# as3320-BandPass-Dev2.net
KiCad netlist of a schematic drawn in EAGLE
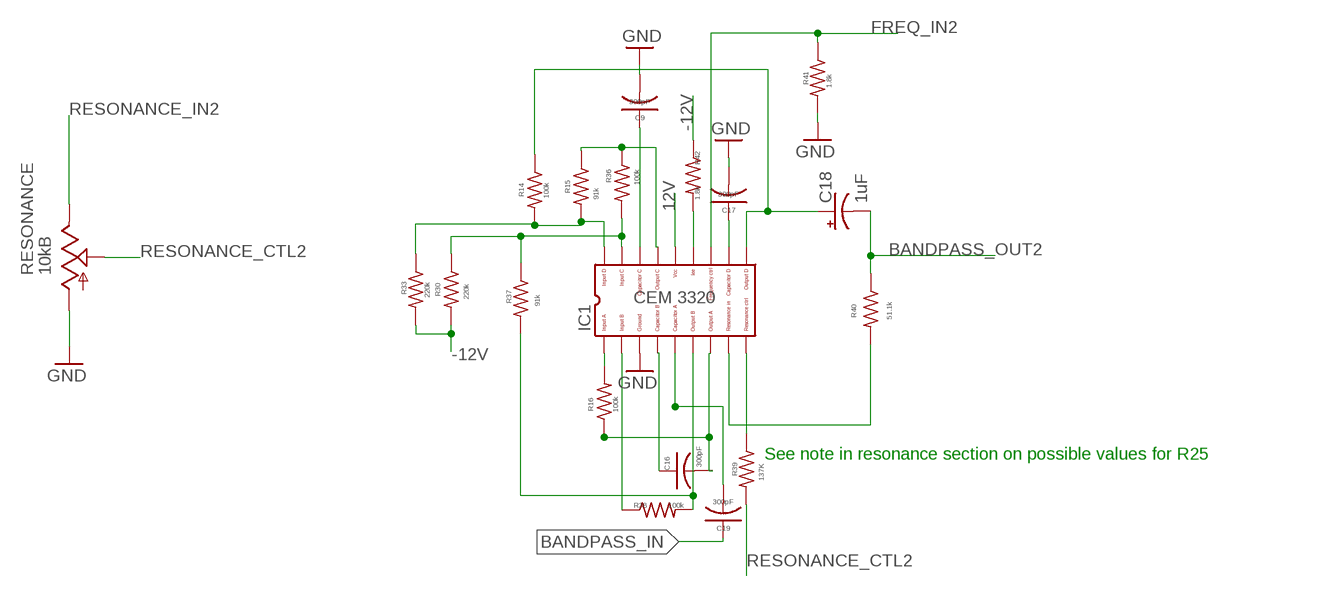
[diagram p0: schematic, sheet 1]
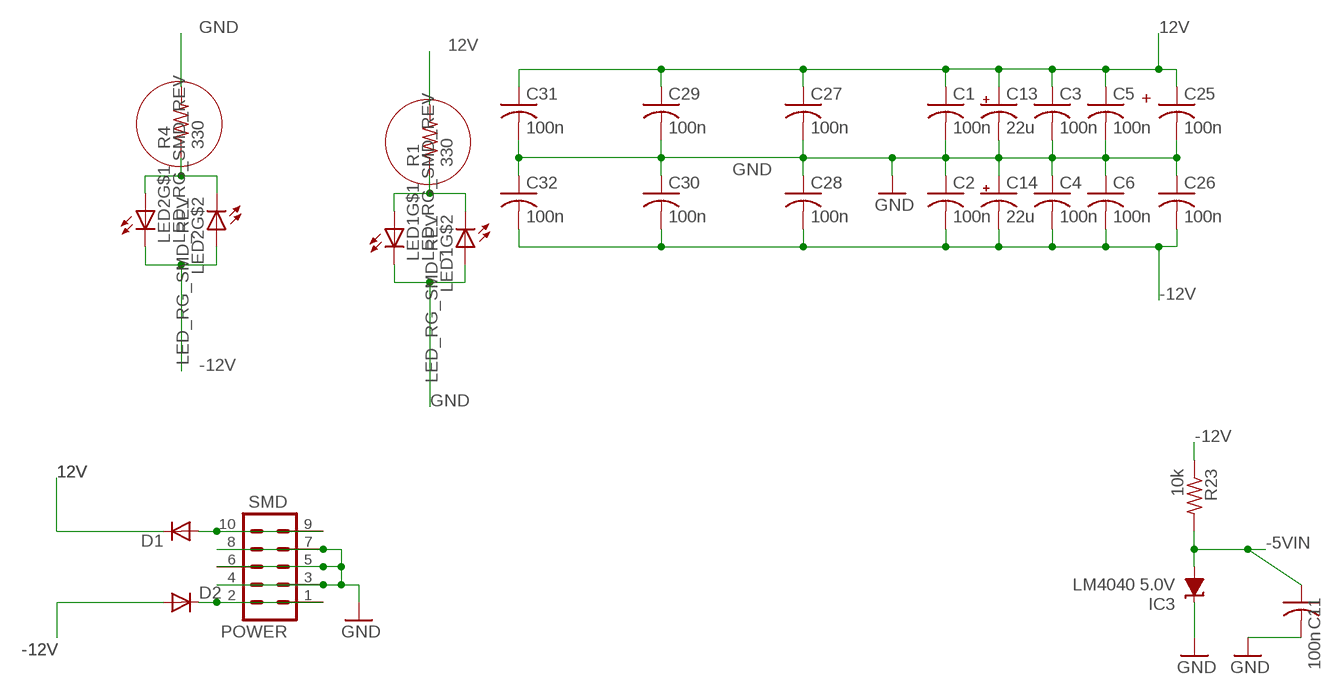
[diagram p1: schematic, sheet 2]
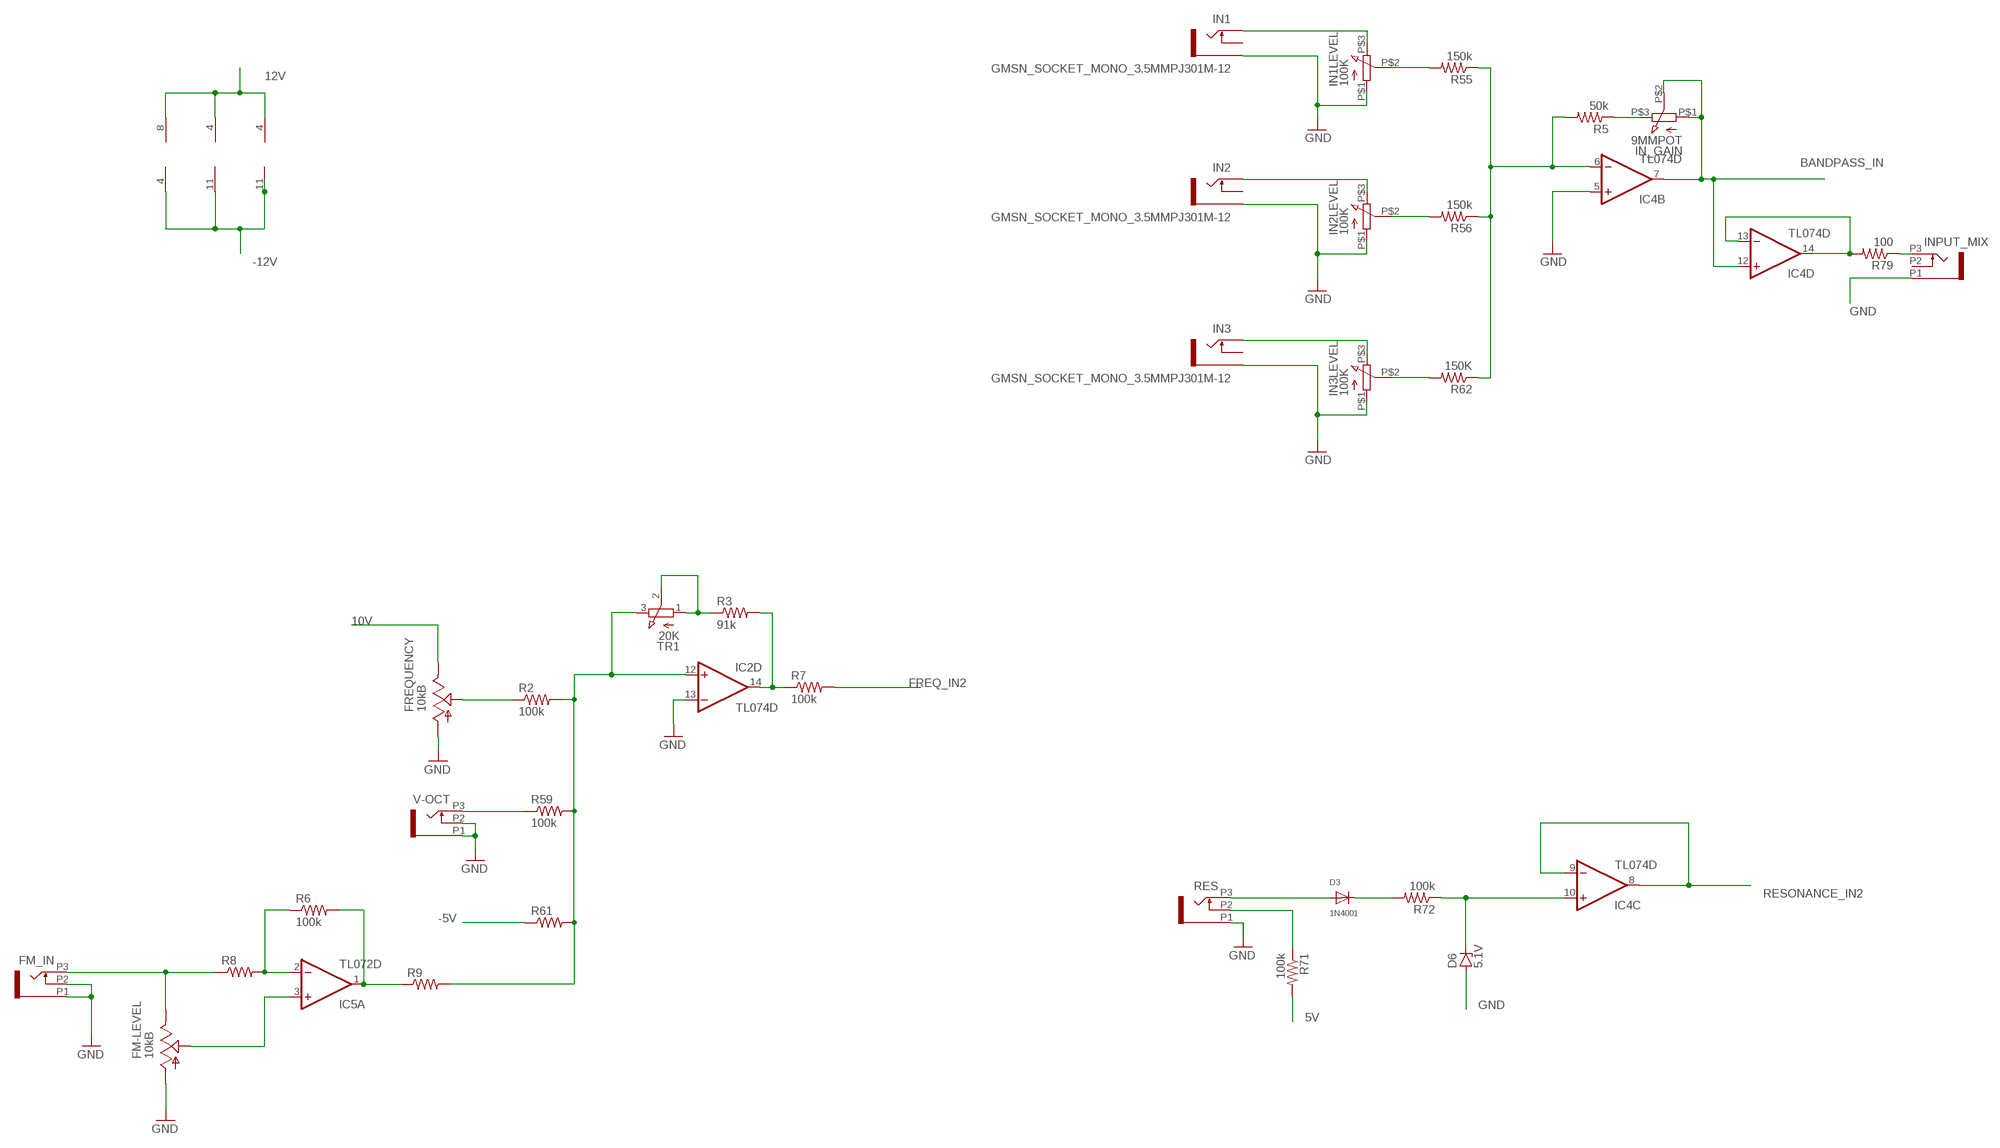
[diagram p2: schematic, sheet 3]
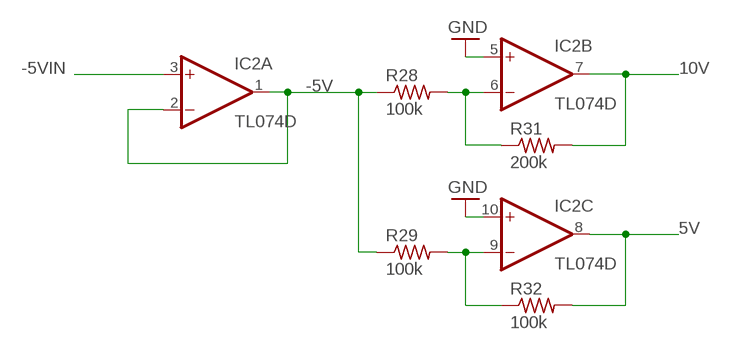
[diagram p3: schematic, sheet 4]
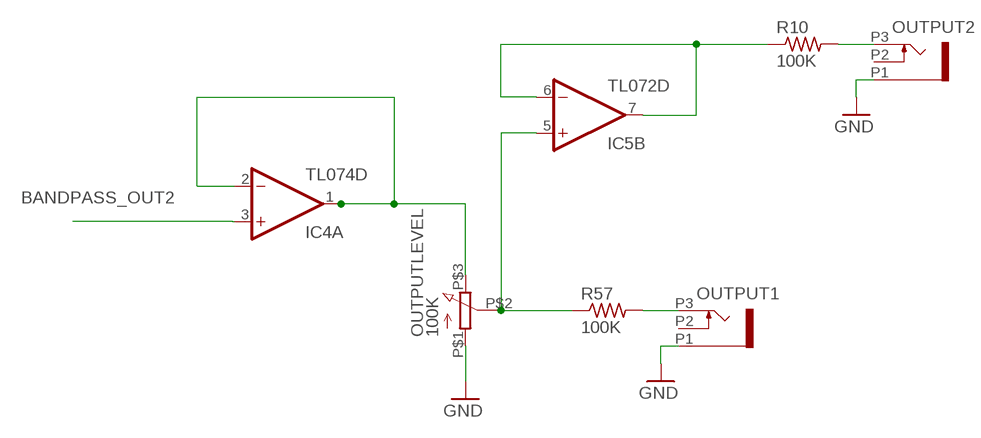
[diagram p4: schematic, sheet 5]

(export (version "E")
  (design (tool "Eeschema 10.0.6"))
  (components
    (comp (ref "C1")
      (value "100n")
      (footprint "eagle-import:C0805K")
      (libsource (lib "eagle-import") (part "C-USC0805K"))
    )
    (comp (ref "C2")
      (value "100n")
      (footprint "eagle-import:C0805K")
      (libsource (lib "eagle-import") (part "C-USC0805K"))
    )
    (comp (ref "C3")
      (value "100n")
      (footprint "eagle-import:C0805K")
      (libsource (lib "eagle-import") (part "C-USC0805K"))
    )
    (comp (ref "C4")
      (value "100n")
      (footprint "eagle-import:C0805K")
      (libsource (lib "eagle-import") (part "C-USC0805K"))
    )
    (comp (ref "C5")
      (value "100n")
      (footprint "eagle-import:C0805K")
      (libsource (lib "eagle-import") (part "C-USC0805K"))
    )
    (comp (ref "C6")
      (value "100n")
      (footprint "eagle-import:C0805K")
      (libsource (lib "eagle-import") (part "C-USC0805K"))
    )
    (comp (ref "C11")
      (value "100n")
      (footprint "eagle-import:GMSN_C0805K")
      (libsource (lib "eagle-import") (part "GMSN_C-USC0805K"))
    )
    (comp (ref "C13")
      (value "22u")
      (footprint "eagle-import:PANASONIC_B")
      (libsource (lib "eagle-import") (part "CPOL-USB"))
    )
    (comp (ref "C14")
      (value "22u")
      (footprint "eagle-import:PANASONIC_B")
      (libsource (lib "eagle-import") (part "CPOL-USB"))
    )
    (comp (ref "C25")
      (value "100n")
      (footprint "eagle-import:C0805K")
      (libsource (lib "eagle-import") (part "C-USC0805K"))
    )
    (comp (ref "C26")
      (value "100n")
      (footprint "eagle-import:C0805K")
      (libsource (lib "eagle-import") (part "C-USC0805K"))
    )
    (comp (ref "C27")
      (value "100n")
      (footprint "eagle-import:C0805K")
      (libsource (lib "eagle-import") (part "C-USC0805K"))
    )
    (comp (ref "C28")
      (value "100n")
      (footprint "eagle-import:C0805K")
      (libsource (lib "eagle-import") (part "C-USC0805K"))
    )
    (comp (ref "C29")
      (value "100n")
      (footprint "eagle-import:C0805K")
      (libsource (lib "eagle-import") (part "C-USC0805K"))
    )
    (comp (ref "C30")
      (value "100n")
      (footprint "eagle-import:C0805K")
      (libsource (lib "eagle-import") (part "C-USC0805K"))
    )
    (comp (ref "C31")
      (value "100n")
      (footprint "eagle-import:C0805K")
      (libsource (lib "eagle-import") (part "C-USC0805K"))
    )
    (comp (ref "C32")
      (value "100n")
      (footprint "eagle-import:C0805K")
      (libsource (lib "eagle-import") (part "C-USC0805K"))
    )
    (comp (ref "D1")
      (value "1N5819HW")
      (footprint "eagle-import:SOD123")
      (libsource (lib "eagle-import") (part "DIODE-SOD123"))
    )
    (comp (ref "D2")
      (value "1N5819HW")
      (footprint "eagle-import:SOD123")
      (libsource (lib "eagle-import") (part "DIODE-SOD123"))
    )
    (comp (ref "IC3")
      (value "LM4040 5.0V")
      (footprint "eagle-import:DBZ_R-PDSO-G3")
      (libsource (lib "eagle-import") (part "LM4041DBZC12"))
    )
    (comp (ref "LED1")
      (value "LED_RG_SMD_REV")
      (footprint "eagle-import:LSG_T77K")
      (fields (field (name "RS-PART") "915-4828"))
      (libsource (lib "eagle-import") (part "LED_RG_SMD_REV"))
    )
    (comp (ref "LED2")
      (value "LED_RG_SMD_REV")
      (footprint "eagle-import:LSG_T77K")
      (libsource (lib "eagle-import") (part "LED_RG_SMD_REV"))
    )
    (comp (ref "POWER")
      (value "SMD")
      (footprint "eagle-import:2X5-SHROUDED_SMD")
      (fields (field (name "RS-PART") "828-1783"))
      (libsource (lib "eagle-import") (part "CONN_05X2SHD_SMD"))
    )
    (comp (ref "R1")
      (value "330")
      (footprint "eagle-import:GMSN_M0805")
      (libsource (lib "eagle-import") (part "GMSN_R-US_M0805"))
    )
    (comp (ref "R4")
      (value "330")
      (footprint "eagle-import:GMSN_M0805")
      (fields (field (name "RS-PART") "915-4828"))
      (libsource (lib "eagle-import") (part "GMSN_R-US_M0805"))
    )
    (comp (ref "R23")
      (value "10k")
      (footprint "eagle-import:GMSN_M0805")
      (libsource (lib "eagle-import") (part "GMSN_R-US_M0805"))
    )
    (comp (ref "C9")
      (value "300pF")
      (footprint "eagle-import:C0805K")
      (libsource (lib "eagle-import") (part "C-USC0805K"))
    )
    (comp (ref "C16")
      (value "300pF")
      (footprint "eagle-import:C0805K")
      (libsource (lib "eagle-import") (part "C-USC0805K"))
    )
    (comp (ref "C17")
      (value "300pF")
      (footprint "eagle-import:C0805K")
      (libsource (lib "eagle-import") (part "C-USC0805K"))
    )
    (comp (ref "C18")
      (value "1uF")
      (footprint "eagle-import:PANASONIC_B")
      (libsource (lib "eagle-import") (part "rcl_334_CPOL-USB"))
    )
    (comp (ref "C19")
      (value "300pF")
      (footprint "eagle-import:C0805K")
      (libsource (lib "eagle-import") (part "C-USC0805K"))
    )
    (comp (ref "IC1")
      (value "CEM3320")
      (footprint "eagle-import:DIL18")
      (libsource (lib "eagle-import") (part "CEM3320"))
    )
    (comp (ref "R14")
      (value "100k")
      (footprint "eagle-import:GMSN_M0805")
      (libsource (lib "eagle-import") (part "GMSN_R-US_M0805"))
    )
    (comp (ref "R15")
      (value "91k")
      (footprint "eagle-import:GMSN_M0805")
      (libsource (lib "eagle-import") (part "GMSN_R-US_M0805"))
    )
    (comp (ref "R16")
      (value "100k")
      (footprint "eagle-import:GMSN_M0805")
      (libsource (lib "eagle-import") (part "GMSN_R-US_M0805"))
    )
    (comp (ref "R30")
      (value "220k")
      (footprint "eagle-import:GMSN_M0805")
      (libsource (lib "eagle-import") (part "GMSN_R-US_M0805"))
    )
    (comp (ref "R33")
      (value "220k")
      (footprint "eagle-import:GMSN_M0805")
      (libsource (lib "eagle-import") (part "GMSN_R-US_M0805"))
    )
    (comp (ref "R36")
      (value "100k")
      (footprint "eagle-import:GMSN_M0805")
      (libsource (lib "eagle-import") (part "GMSN_R-US_M0805"))
    )
    (comp (ref "R37")
      (value "91k")
      (footprint "eagle-import:GMSN_M0805")
      (libsource (lib "eagle-import") (part "GMSN_R-US_M0805"))
    )
    (comp (ref "R38")
      (value "100k")
      (footprint "eagle-import:GMSN_M0805")
      (libsource (lib "eagle-import") (part "GMSN_R-US_M0805"))
    )
    (comp (ref "R39")
      (value "137K")
      (footprint "eagle-import:GMSN_M0805")
      (libsource (lib "eagle-import") (part "GMSN_R-US_M0805"))
    )
    (comp (ref "R40")
      (value "51.1k")
      (footprint "eagle-import:GMSN_M0805")
      (libsource (lib "eagle-import") (part "GMSN_R-US_M0805"))
    )
    (comp (ref "R41")
      (value "1.8k")
      (footprint "eagle-import:GMSN_M0805")
      (libsource (lib "eagle-import") (part "GMSN_R-US_M0805"))
    )
    (comp (ref "R42")
      (value "1.8k")
      (footprint "eagle-import:GMSN_M0805")
      (libsource (lib "eagle-import") (part "GMSN_R-US_M0805"))
    )
    (comp (ref "RESONANCE")
      (value "10kB")
      (footprint "eagle-import:ALPS_POT_VERTICAL")
      (libsource (lib "eagle-import") (part "POT_USVERTICAL"))
    )
    (comp (ref "D3")
      (value "1N4001")
      (footprint "eagle-import:SMADIODE")
      (libsource (lib "eagle-import") (part "DIODESMA"))
    )
    (comp (ref "D6")
      (value "5.1V")
      (footprint "eagle-import:SOT23")
      (fields (field (name "RS-PART") "816-7962"))
      (libsource (lib "eagle-import") (part "ZENER-DIODESOT23"))
    )
    (comp (ref "FM-LEVEL")
      (value "10kB")
      (footprint "eagle-import:ALPS_POT_VERTICAL")
      (libsource (lib "eagle-import") (part "POT_USVERTICAL"))
    )
    (comp (ref "FM_IN")
      (value "PJ301_THONKICONN6")
      (footprint "eagle-import:WQP_PJ_301M6")
      (libsource (lib "eagle-import") (part "PJ301_THONKICONN6"))
    )
    (comp (ref "FREQUENCY")
      (value "10kB")
      (footprint "eagle-import:ALPS_POT_VERTICAL")
      (libsource (lib "eagle-import") (part "POT_USVERTICAL"))
    )
    (comp (ref "IC2")
      (value "TL074D")
      (footprint "eagle-import:SO14")
      (libsource (lib "eagle-import") (part "linear_262_TL074D"))
    )
    (comp (ref "IC4")
      (value "TL074D")
      (footprint "eagle-import:SO14")
      (libsource (lib "eagle-import") (part "TL074D"))
    )
    (comp (ref "IC5")
      (value "TL072D")
      (footprint "eagle-import:SO08")
      (libsource (lib "eagle-import") (part "TL072D"))
    )
    (comp (ref "IN1")
      (value "GMSN_SOCKET_MONO_3.5MMPJ301M-12")
      (footprint "eagle-import:GMSN_PJ301M-12")
      (libsource (lib "eagle-import") (part "GMSN_SOCKET_MONO_3.5MMPJ301M-12"))
    )
    (comp (ref "IN1LEVEL")
      (value "100K")
      (footprint "eagle-import:POT")
      (libsource (lib "eagle-import") (part "9MMPOT"))
    )
    (comp (ref "IN2")
      (value "GMSN_SOCKET_MONO_3.5MMPJ301M-12")
      (footprint "eagle-import:GMSN_PJ301M-12")
      (libsource (lib "eagle-import") (part "GMSN_SOCKET_MONO_3.5MMPJ301M-12"))
    )
    (comp (ref "IN2LEVEL")
      (value "100K")
      (footprint "eagle-import:POT")
      (libsource (lib "eagle-import") (part "9MMPOT"))
    )
    (comp (ref "IN3")
      (value "GMSN_SOCKET_MONO_3.5MMPJ301M-12")
      (footprint "eagle-import:GMSN_PJ301M-12")
      (libsource (lib "eagle-import") (part "GMSN_SOCKET_MONO_3.5MMPJ301M-12"))
    )
    (comp (ref "IN3LEVEL")
      (value "100K")
      (footprint "eagle-import:POT")
      (libsource (lib "eagle-import") (part "9MMPOT"))
    )
    (comp (ref "INPUT_MIX")
      (value "PJ301_THONKICONN6")
      (footprint "eagle-import:WQP_PJ_301M6")
      (libsource (lib "eagle-import") (part "PJ301_THONKICONN6"))
    )
    (comp (ref "IN_GAIN")
      (value "9MMPOT")
      (footprint "eagle-import:POT")
      (libsource (lib "eagle-import") (part "9MMPOT"))
    )
    (comp (ref "R2")
      (value "100k")
      (footprint "eagle-import:GMSN_M0805")
      (libsource (lib "eagle-import") (part "GMSN_R-US_M0805"))
    )
    (comp (ref "R3")
      (value "91k")
      (footprint "eagle-import:GMSN_M0805")
      (libsource (lib "eagle-import") (part "GMSN_R-US_M0805"))
    )
    (comp (ref "R5")
      (value "50k")
      (footprint "eagle-import:GMSN_M0805")
      (libsource (lib "eagle-import") (part "GMSN_R-US_M0805"))
    )
    (comp (ref "R6")
      (value "100k")
      (footprint "eagle-import:GMSN_M0805")
      (libsource (lib "eagle-import") (part "GMSN_R-US_M0805"))
    )
    (comp (ref "R7")
      (value "100k")
      (footprint "eagle-import:GMSN_M0805")
      (libsource (lib "eagle-import") (part "GMSN_R-US_M0805"))
    )
    (comp (ref "R8")
      (value "62k")
      (footprint "eagle-import:GMSN_M0805")
      (libsource (lib "eagle-import") (part "GMSN_R-US_M0805"))
    )
    (comp (ref "R9")
      (value "62k")
      (footprint "eagle-import:GMSN_M0805")
      (libsource (lib "eagle-import") (part "GMSN_R-US_M0805"))
    )
    (comp (ref "R55")
      (value "150k")
      (footprint "eagle-import:R0805")
      (libsource (lib "eagle-import") (part "GMSN_R-US_R0805"))
    )
    (comp (ref "R56")
      (value "150k")
      (footprint "eagle-import:R0805")
      (libsource (lib "eagle-import") (part "GMSN_R-US_R0805"))
    )
    (comp (ref "R59")
      (value "100k")
      (footprint "eagle-import:GMSN_M0805")
      (libsource (lib "eagle-import") (part "GMSN_R-US_M0805"))
    )
    (comp (ref "R61")
      (value "62k")
      (footprint "eagle-import:GMSN_M0805")
      (libsource (lib "eagle-import") (part "GMSN_R-US_M0805"))
    )
    (comp (ref "R62")
      (value "150K")
      (footprint "eagle-import:R0805")
      (libsource (lib "eagle-import") (part "GMSN_R-US_R0805"))
    )
    (comp (ref "R71")
      (value "100k")
      (footprint "eagle-import:R0805")
      (libsource (lib "eagle-import") (part "GMSN_R-US_R0805"))
    )
    (comp (ref "R72")
      (value "100k")
      (footprint "eagle-import:GMSN_M0805")
      (libsource (lib "eagle-import") (part "GMSN_R-US_M0805"))
    )
    (comp (ref "R79")
      (value "100")
      (footprint "eagle-import:GMSN_M0805")
      (libsource (lib "eagle-import") (part "GMSN_R-US_M0805"))
    )
    (comp (ref "RES")
      (value "PJ301_THONKICONN6")
      (footprint "eagle-import:WQP_PJ_301M6")
      (libsource (lib "eagle-import") (part "PJ301_THONKICONN6"))
    )
    (comp (ref "TR1")
      (value "20K")
      (footprint "eagle-import:TRIMMER_TH3")
      (libsource (lib "eagle-import") (part "TRIMMER_TH3"))
    )
    (comp (ref "V-OCT")
      (value "PJ301_THONKICONN6")
      (footprint "eagle-import:WQP_PJ_301M6")
      (libsource (lib "eagle-import") (part "PJ301_THONKICONN6"))
    )
    (comp (ref "OUTPUT1")
      (value "PJ301_THONKICONN6")
      (footprint "eagle-import:WQP_PJ_301M6")
      (libsource (lib "eagle-import") (part "PJ301_THONKICONN6"))
    )
    (comp (ref "OUTPUT2")
      (value "PJ301_THONKICONN6")
      (footprint "eagle-import:WQP_PJ_301M6")
      (libsource (lib "eagle-import") (part "PJ301_THONKICONN6"))
    )
    (comp (ref "OUTPUTLEVEL")
      (value "100K")
      (footprint "eagle-import:POT")
      (libsource (lib "eagle-import") (part "9MMPOT"))
    )
    (comp (ref "R10")
      (value "100K")
      (footprint "eagle-import:GMSN_M0805")
      (libsource (lib "eagle-import") (part "GMSN_R-US_M0805"))
    )
    (comp (ref "R57")
      (value "100K")
      (footprint "eagle-import:GMSN_M0805")
      (libsource (lib "eagle-import") (part "GMSN_R-US_M0805"))
    )
    (comp (ref "R28")
      (value "100k")
      (footprint "eagle-import:GMSN_M0805")
      (libsource (lib "eagle-import") (part "GMSN_R-US_M0805"))
    )
    (comp (ref "R29")
      (value "100k")
      (footprint "eagle-import:GMSN_M0805")
      (libsource (lib "eagle-import") (part "GMSN_R-US_M0805"))
    )
    (comp (ref "R31")
      (value "200k")
      (footprint "eagle-import:GMSN_M0805")
      (libsource (lib "eagle-import") (part "GMSN_R-US_M0805"))
    )
    (comp (ref "R32")
      (value "100k")
      (footprint "eagle-import:GMSN_M0805")
      (libsource (lib "eagle-import") (part "GMSN_R-US_M0805"))
    )
  )
  (nets
    (net (code "1") (name "-5V") (class "Default")
      (node (ref "IC2") (pin "1") (pinfunction "OUT_1") (pintype "output"))
      (node (ref "IC2") (pin "2") (pinfunction "-IN_2") (pintype "input"))
      (node (ref "R28") (pin "1") (pinfunction "1_1") (pintype "passive"))
      (node (ref "R29") (pin "1") (pinfunction "1_1") (pintype "passive"))
      (node (ref "R61") (pin "1") (pinfunction "1_1") (pintype "passive"))
    )
    (net (code "2") (name "-5VIN") (class "Default")
      (node (ref "C11") (pin "1") (pinfunction "1_1") (pintype "passive"))
      (node (ref "IC2") (pin "3") (pinfunction "+IN_3") (pintype "input"))
      (node (ref "IC3") (pin "2") (pinfunction "A_2") (pintype "passive"))
      (node (ref "R23") (pin "2") (pinfunction "2_2") (pintype "passive"))
    )
    (net (code "3") (name "-12V") (class "Default")
      (node (ref "C14") (pin "-") (pinfunction "-_-") (pintype "passive"))
      (node (ref "C2") (pin "2") (pinfunction "2_2") (pintype "passive"))
      (node (ref "C26") (pin "2") (pinfunction "2_2") (pintype "passive"))
      (node (ref "C28") (pin "2") (pinfunction "2_2") (pintype "passive"))
      (node (ref "C30") (pin "2") (pinfunction "2_2") (pintype "passive"))
      (node (ref "C32") (pin "2") (pinfunction "2_2") (pintype "passive"))
      (node (ref "C4") (pin "2") (pinfunction "2_2") (pintype "passive"))
      (node (ref "C6") (pin "2") (pinfunction "2_2") (pintype "passive"))
      (node (ref "D2") (pin "A") (pinfunction "A_A") (pintype "passive"))
      (node (ref "IC2") (pin "11") (pinfunction "V-_11") (pintype "power_in"))
      (node (ref "IC4") (pin "11") (pinfunction "V-_11") (pintype "power_in"))
      (node (ref "IC5") (pin "4") (pinfunction "V-_4") (pintype "power_in"))
      (node (ref "LED2") (pin "1") (pinfunction "C_1") (pintype "passive"))
      (node (ref "LED2") (pin "4") (pinfunction "A_4") (pintype "passive"))
      (node (ref "R23") (pin "1") (pinfunction "1_1") (pintype "passive"))
      (node (ref "R30") (pin "2") (pinfunction "2_2") (pintype "passive"))
      (node (ref "R33") (pin "2") (pinfunction "2_2") (pintype "passive"))
      (node (ref "R42") (pin "1") (pinfunction "1_1") (pintype "passive"))
    )
    (net (code "4") (name "5V") (class "Default")
      (node (ref "IC2") (pin "8") (pinfunction "OUT_8") (pintype "output"))
      (node (ref "R32") (pin "2") (pinfunction "2_2") (pintype "passive"))
      (node (ref "R71") (pin "2") (pinfunction "2_2") (pintype "passive"))
    )
    (net (code "5") (name "10V") (class "Default")
      (node (ref "FREQUENCY") (pin "P$1") (pinfunction "E_P$1") (pintype "passive"))
      (node (ref "IC2") (pin "7") (pinfunction "OUT_7") (pintype "output"))
      (node (ref "R31") (pin "2") (pinfunction "2_2") (pintype "passive"))
    )
    (net (code "6") (name "12V") (class "Default")
      (node (ref "C1") (pin "1") (pinfunction "1_1") (pintype "passive"))
      (node (ref "C13") (pin "+") (pinfunction "+_+") (pintype "passive"))
      (node (ref "C25") (pin "1") (pinfunction "1_1") (pintype "passive"))
      (node (ref "C27") (pin "1") (pinfunction "1_1") (pintype "passive"))
      (node (ref "C29") (pin "1") (pinfunction "1_1") (pintype "passive"))
      (node (ref "C3") (pin "1") (pinfunction "1_1") (pintype "passive"))
      (node (ref "C31") (pin "1") (pinfunction "1_1") (pintype "passive"))
      (node (ref "C5") (pin "1") (pinfunction "1_1") (pintype "passive"))
      (node (ref "D1") (pin "C") (pinfunction "C_C") (pintype "passive"))
      (node (ref "IC1") (pin "14") (pinfunction "14_14") (pintype "power_in"))
      (node (ref "IC2") (pin "4") (pinfunction "V+_4") (pintype "power_in"))
      (node (ref "IC4") (pin "4") (pinfunction "V+_4") (pintype "power_in"))
      (node (ref "IC5") (pin "8") (pinfunction "V+_8") (pintype "power_in"))
      (node (ref "R1") (pin "2") (pinfunction "2_2") (pintype "passive"))
    )
    (net (code "7") (name "BANDPASS_IN") (class "Default")
      (node (ref "C19") (pin "1") (pinfunction "1_1") (pintype "passive"))
      (node (ref "IC4") (pin "12") (pinfunction "+IN_12") (pintype "input"))
      (node (ref "IC4") (pin "7") (pinfunction "OUT_7") (pintype "output"))
      (node (ref "IN_GAIN") (pin "P$1") (pinfunction "1_P$1") (pintype "passive"))
      (node (ref "IN_GAIN") (pin "P$2") (pinfunction "2_P$2") (pintype "passive"))
    )
    (net (code "8") (name "BANDPASS_OUT2") (class "Default")
      (node (ref "C18") (pin "-") (pinfunction "-_-") (pintype "passive"))
      (node (ref "IC4") (pin "3") (pinfunction "+IN_3") (pintype "input"))
      (node (ref "R40") (pin "1") (pinfunction "1_1") (pintype "passive"))
    )
    (net (code "9") (name "FREQ_IN2") (class "Default")
      (node (ref "IC1") (pin "12") (pinfunction "12_12") (pintype "bidirectional"))
      (node (ref "R41") (pin "1") (pinfunction "1_1") (pintype "passive"))
      (node (ref "R7") (pin "2") (pinfunction "2_2") (pintype "passive"))
    )
    (net (code "10") (name "GND") (class "Default")
      (node (ref "C1") (pin "2") (pinfunction "2_2") (pintype "passive"))
      (node (ref "C11") (pin "2") (pinfunction "2_2") (pintype "passive"))
      (node (ref "C13") (pin "-") (pinfunction "-_-") (pintype "passive"))
      (node (ref "C14") (pin "+") (pinfunction "+_+") (pintype "passive"))
      (node (ref "C17") (pin "2") (pinfunction "2_2") (pintype "passive"))
      (node (ref "C2") (pin "1") (pinfunction "1_1") (pintype "passive"))
      (node (ref "C25") (pin "2") (pinfunction "2_2") (pintype "passive"))
      (node (ref "C26") (pin "1") (pinfunction "1_1") (pintype "passive"))
      (node (ref "C27") (pin "2") (pinfunction "2_2") (pintype "passive"))
      (node (ref "C28") (pin "1") (pinfunction "1_1") (pintype "passive"))
      (node (ref "C29") (pin "2") (pinfunction "2_2") (pintype "passive"))
      (node (ref "C3") (pin "2") (pinfunction "2_2") (pintype "passive"))
      (node (ref "C30") (pin "1") (pinfunction "1_1") (pintype "passive"))
      (node (ref "C31") (pin "2") (pinfunction "2_2") (pintype "passive"))
      (node (ref "C32") (pin "1") (pinfunction "1_1") (pintype "passive"))
      (node (ref "C4") (pin "1") (pinfunction "1_1") (pintype "passive"))
      (node (ref "C5") (pin "2") (pinfunction "2_2") (pintype "passive"))
      (node (ref "C6") (pin "1") (pinfunction "1_1") (pintype "passive"))
      (node (ref "C9") (pin "2") (pinfunction "2_2") (pintype "passive"))
      (node (ref "D6") (pin "1") (pinfunction "A_1") (pintype "passive"))
      (node (ref "FM-LEVEL") (pin "P$3") (pinfunction "A_P$3") (pintype "passive"))
      (node (ref "FM_IN") (pin "P1") (pinfunction "1_P1") (pintype "passive"))
      (node (ref "FM_IN") (pin "P2") (pinfunction "2_P2") (pintype "passive"))
      (node (ref "FREQUENCY") (pin "P$3") (pinfunction "A_P$3") (pintype "passive"))
      (node (ref "IC1") (pin "3") (pinfunction "3_3") (pintype "power_in"))
      (node (ref "IC2") (pin "10") (pinfunction "+IN_10") (pintype "input"))
      (node (ref "IC2") (pin "13") (pinfunction "-IN_13") (pintype "input"))
      (node (ref "IC2") (pin "5") (pinfunction "+IN_5") (pintype "input"))
      (node (ref "IC3") (pin "1") (pinfunction "C_1") (pintype "passive"))
      (node (ref "IC4") (pin "5") (pinfunction "+IN_5") (pintype "input"))
      (node (ref "IN1") (pin "GND") (pinfunction "SLEEVE_GND") (pintype "passive"))
      (node (ref "IN1LEVEL") (pin "P$1") (pinfunction "1_P$1") (pintype "passive"))
      (node (ref "IN2") (pin "GND") (pinfunction "SLEEVE_GND") (pintype "passive"))
      (node (ref "IN2LEVEL") (pin "P$1") (pinfunction "1_P$1") (pintype "passive"))
      (node (ref "IN3") (pin "GND") (pinfunction "SLEEVE_GND") (pintype "passive"))
      (node (ref "IN3LEVEL") (pin "P$1") (pinfunction "1_P$1") (pintype "passive"))
      (node (ref "INPUT_MIX") (pin "P1") (pinfunction "1_P1") (pintype "passive"))
      (node (ref "LED1") (pin "1") (pinfunction "C_1") (pintype "passive"))
      (node (ref "LED1") (pin "4") (pinfunction "A_4") (pintype "passive"))
      (node (ref "OUTPUT1") (pin "P1") (pinfunction "1_P1") (pintype "passive"))
      (node (ref "OUTPUT2") (pin "P1") (pinfunction "1_P1") (pintype "passive"))
      (node (ref "OUTPUTLEVEL") (pin "P$1") (pinfunction "1_P$1") (pintype "passive"))
      (node (ref "POWER") (pin "3") (pinfunction "3_3") (pintype "passive"))
      (node (ref "POWER") (pin "4") (pinfunction "4_4") (pintype "passive"))
      (node (ref "POWER") (pin "5") (pinfunction "5_5") (pintype "passive"))
      (node (ref "POWER") (pin "6") (pinfunction "6_6") (pintype "passive"))
      (node (ref "POWER") (pin "7") (pinfunction "7_7") (pintype "passive"))
      (node (ref "POWER") (pin "8") (pinfunction "8_8") (pintype "passive"))
      (node (ref "R4") (pin "2") (pinfunction "2_2") (pintype "passive"))
      (node (ref "R41") (pin "2") (pinfunction "2_2") (pintype "passive"))
      (node (ref "RES") (pin "P1") (pinfunction "1_P1") (pintype "passive"))
      (node (ref "RESONANCE") (pin "P$3") (pinfunction "A_P$3") (pintype "passive"))
      (node (ref "V-OCT") (pin "P1") (pinfunction "1_P1") (pintype "passive"))
      (node (ref "V-OCT") (pin "P2") (pinfunction "2_P2") (pintype "passive"))
    )
    (net (code "11") (name "Net-(C9-Pad1)") (class "Default")
      (node (ref "C9") (pin "1") (pinfunction "1_1") (pintype "passive"))
      (node (ref "IC1") (pin "16") (pinfunction "16_16") (pintype "bidirectional"))
    )
    (net (code "12") (name "Net-(C16-Pad1)") (class "Default")
      (node (ref "C16") (pin "1") (pinfunction "1_1") (pintype "passive"))
      (node (ref "IC1") (pin "4") (pinfunction "4_4") (pintype "bidirectional"))
    )
    (net (code "13") (name "Net-(C16-Pad2)") (class "Default")
      (node (ref "C16") (pin "2") (pinfunction "2_2") (pintype "passive"))
      (node (ref "IC1") (pin "7") (pinfunction "7_7") (pintype "output"))
      (node (ref "R16") (pin "1") (pinfunction "1_1") (pintype "passive"))
    )
    (net (code "14") (name "Net-(C17-Pad1)") (class "Default")
      (node (ref "C17") (pin "1") (pinfunction "1_1") (pintype "passive"))
      (node (ref "IC1") (pin "11") (pinfunction "11_11") (pintype "output"))
    )
    (net (code "15") (name "Net-(C18-Pad+)") (class "Default")
      (node (ref "C18") (pin "+") (pinfunction "+_+") (pintype "passive"))
      (node (ref "IC1") (pin "10") (pinfunction "10_10") (pintype "output"))
      (node (ref "R14") (pin "1") (pinfunction "1_1") (pintype "passive"))
    )
    (net (code "16") (name "Net-(C19-Pad2)") (class "Default")
      (node (ref "C19") (pin "2") (pinfunction "2_2") (pintype "passive"))
      (node (ref "IC1") (pin "5") (pinfunction "5_5") (pintype "bidirectional"))
    )
    (net (code "17") (name "Net-(D1-PadA)") (class "Default")
      (node (ref "D1") (pin "A") (pinfunction "A_A") (pintype "passive"))
      (node (ref "POWER") (pin "10") (pinfunction "10_10") (pintype "passive"))
      (node (ref "POWER") (pin "9") (pinfunction "9_9") (pintype "passive"))
    )
    (net (code "18") (name "Net-(D2-PadC)") (class "Default")
      (node (ref "D2") (pin "C") (pinfunction "C_C") (pintype "passive"))
      (node (ref "POWER") (pin "1") (pinfunction "1_1") (pintype "passive"))
      (node (ref "POWER") (pin "2") (pinfunction "2_2") (pintype "passive"))
    )
    (net (code "19") (name "Net-(D3-PadC)") (class "Default")
      (node (ref "D3") (pin "C") (pinfunction "C_C") (pintype "passive"))
      (node (ref "R72") (pin "2") (pinfunction "2_2") (pintype "passive"))
    )
    (net (code "20") (name "Net-(D6-C)") (class "Default")
      (node (ref "D6") (pin "3") (pinfunction "C_3") (pintype "passive"))
      (node (ref "IC4") (pin "10") (pinfunction "+IN_10") (pintype "input"))
      (node (ref "R72") (pin "1") (pinfunction "1_1") (pintype "passive"))
    )
    (net (code "21") (name "Net-(FM-LEVEL-E)") (class "Default")
      (node (ref "FM-LEVEL") (pin "P$1") (pinfunction "E_P$1") (pintype "passive"))
      (node (ref "FM_IN") (pin "P3") (pinfunction "3_P3") (pintype "passive"))
      (node (ref "R8") (pin "1") (pinfunction "1_1") (pintype "passive"))
    )
    (net (code "22") (name "Net-(FM-LEVEL-S)") (class "Default")
      (node (ref "FM-LEVEL") (pin "P$2") (pinfunction "S_P$2") (pintype "passive"))
      (node (ref "IC5") (pin "3") (pinfunction "+IN_3") (pintype "input"))
    )
    (net (code "23") (name "Net-(FREQUENCY-S)") (class "Default")
      (node (ref "FREQUENCY") (pin "P$2") (pinfunction "S_P$2") (pintype "passive"))
      (node (ref "R2") (pin "1") (pinfunction "1_1") (pintype "passive"))
    )
    (net (code "24") (name "Net-(IC1-Pad1)") (class "Default")
      (node (ref "IC1") (pin "1") (pinfunction "1_1") (pintype "input"))
      (node (ref "R16") (pin "2") (pinfunction "2_2") (pintype "passive"))
    )
    (net (code "25") (name "Net-(IC1-Pad2)") (class "Default")
      (node (ref "IC1") (pin "2") (pinfunction "2_2") (pintype "input"))
      (node (ref "R38") (pin "1") (pinfunction "1_1") (pintype "passive"))
    )
    (net (code "26") (name "Net-(IC1-Pad6)") (class "Default")
      (node (ref "IC1") (pin "6") (pinfunction "6_6") (pintype "output"))
      (node (ref "R37") (pin "2") (pinfunction "2_2") (pintype "passive"))
      (node (ref "R38") (pin "2") (pinfunction "2_2") (pintype "passive"))
    )
    (net (code "27") (name "Net-(IC1-Pad8)") (class "Default")
      (node (ref "IC1") (pin "8") (pinfunction "8_8") (pintype "input"))
      (node (ref "R40") (pin "2") (pinfunction "2_2") (pintype "passive"))
    )
    (net (code "28") (name "Net-(IC1-Pad9)") (class "Default")
      (node (ref "IC1") (pin "9") (pinfunction "9_9") (pintype "input"))
      (node (ref "R39") (pin "1") (pinfunction "1_1") (pintype "passive"))
    )
    (net (code "29") (name "Net-(IC1-Pad13)") (class "Default")
      (node (ref "IC1") (pin "13") (pinfunction "13_13") (pintype "power_in"))
      (node (ref "R42") (pin "2") (pinfunction "2_2") (pintype "passive"))
    )
    (net (code "30") (name "Net-(IC1-Pad15)") (class "Default")
      (node (ref "IC1") (pin "15") (pinfunction "15_15") (pintype "output"))
      (node (ref "R15") (pin "1") (pinfunction "1_1") (pintype "passive"))
      (node (ref "R36") (pin "1") (pinfunction "1_1") (pintype "passive"))
    )
    (net (code "31") (name "Net-(IC1-Pad17)") (class "Default")
      (node (ref "IC1") (pin "17") (pinfunction "17_17") (pintype "input"))
      (node (ref "R30") (pin "1") (pinfunction "1_1") (pintype "passive"))
      (node (ref "R36") (pin "2") (pinfunction "2_2") (pintype "passive"))
      (node (ref "R37") (pin "1") (pinfunction "1_1") (pintype "passive"))
    )
    (net (code "32") (name "Net-(IC1-Pad18)") (class "Default")
      (node (ref "IC1") (pin "18") (pinfunction "18_18") (pintype "input"))
      (node (ref "R14") (pin "2") (pinfunction "2_2") (pintype "passive"))
      (node (ref "R15") (pin "2") (pinfunction "2_2") (pintype "passive"))
      (node (ref "R33") (pin "1") (pinfunction "1_1") (pintype "passive"))
    )
    (net (code "33") (name "Net-(IC2B--IN)") (class "Default")
      (node (ref "IC2") (pin "6") (pinfunction "-IN_6") (pintype "input"))
      (node (ref "R28") (pin "2") (pinfunction "2_2") (pintype "passive"))
      (node (ref "R31") (pin "1") (pinfunction "1_1") (pintype "passive"))
    )
    (net (code "34") (name "Net-(IC2C--IN)") (class "Default")
      (node (ref "IC2") (pin "9") (pinfunction "-IN_9") (pintype "input"))
      (node (ref "R29") (pin "2") (pinfunction "2_2") (pintype "passive"))
      (node (ref "R32") (pin "1") (pinfunction "1_1") (pintype "passive"))
    )
    (net (code "35") (name "Net-(IC2D-+IN)") (class "Default")
      (node (ref "IC2") (pin "12") (pinfunction "+IN_12") (pintype "input"))
      (node (ref "R2") (pin "2") (pinfunction "2_2") (pintype "passive"))
      (node (ref "R59") (pin "2") (pinfunction "2_2") (pintype "passive"))
      (node (ref "R61") (pin "2") (pinfunction "2_2") (pintype "passive"))
      (node (ref "R9") (pin "2") (pinfunction "2_2") (pintype "passive"))
      (node (ref "TR1") (pin "3") (pinfunction "3_3") (pintype "passive"))
    )
    (net (code "36") (name "Net-(IC2D-OUT)") (class "Default")
      (node (ref "IC2") (pin "14") (pinfunction "OUT_14") (pintype "output"))
      (node (ref "R3") (pin "2") (pinfunction "2_2") (pintype "passive"))
      (node (ref "R7") (pin "1") (pinfunction "1_1") (pintype "passive"))
    )
    (net (code "37") (name "Net-(IC4A--IN)") (class "Default")
      (node (ref "IC4") (pin "1") (pinfunction "OUT_1") (pintype "output"))
      (node (ref "IC4") (pin "2") (pinfunction "-IN_2") (pintype "input"))
      (node (ref "OUTPUTLEVEL") (pin "P$3") (pinfunction "3_P$3") (pintype "passive"))
    )
    (net (code "38") (name "Net-(IC4B--IN)") (class "Default")
      (node (ref "IC4") (pin "6") (pinfunction "-IN_6") (pintype "input"))
      (node (ref "R5") (pin "2") (pinfunction "2_2") (pintype "passive"))
      (node (ref "R55") (pin "1") (pinfunction "1_1") (pintype "passive"))
      (node (ref "R56") (pin "1") (pinfunction "1_1") (pintype "passive"))
      (node (ref "R62") (pin "1") (pinfunction "1_1") (pintype "passive"))
    )
    (net (code "39") (name "Net-(IC4D--IN)") (class "Default")
      (node (ref "IC4") (pin "13") (pinfunction "-IN_13") (pintype "input"))
      (node (ref "IC4") (pin "14") (pinfunction "OUT_14") (pintype "output"))
      (node (ref "R79") (pin "2") (pinfunction "2_2") (pintype "passive"))
    )
    (net (code "40") (name "Net-(IC5A--IN)") (class "Default")
      (node (ref "IC5") (pin "2") (pinfunction "-IN_2") (pintype "input"))
      (node (ref "R6") (pin "1") (pinfunction "1_1") (pintype "passive"))
      (node (ref "R8") (pin "2") (pinfunction "2_2") (pintype "passive"))
    )
    (net (code "41") (name "Net-(IC5A-OUT)") (class "Default")
      (node (ref "IC5") (pin "1") (pinfunction "OUT_1") (pintype "output"))
      (node (ref "R6") (pin "2") (pinfunction "2_2") (pintype "passive"))
      (node (ref "R9") (pin "1") (pinfunction "1_1") (pintype "passive"))
    )
    (net (code "42") (name "Net-(IC5B-+IN)") (class "Default")
      (node (ref "IC5") (pin "5") (pinfunction "+IN_5") (pintype "input"))
      (node (ref "OUTPUTLEVEL") (pin "P$2") (pinfunction "2_P$2") (pintype "passive"))
      (node (ref "R57") (pin "1") (pinfunction "1_1") (pintype "passive"))
    )
    (net (code "43") (name "Net-(IC5B--IN)") (class "Default")
      (node (ref "IC5") (pin "6") (pinfunction "-IN_6") (pintype "input"))
      (node (ref "IC5") (pin "7") (pinfunction "OUT_7") (pintype "output"))
      (node (ref "R10") (pin "1") (pinfunction "1_1") (pintype "passive"))
    )
    (net (code "44") (name "Net-(IN1LEVEL-2)") (class "Default")
      (node (ref "IN1LEVEL") (pin "P$2") (pinfunction "2_P$2") (pintype "passive"))
      (node (ref "R55") (pin "2") (pinfunction "2_2") (pintype "passive"))
    )
    (net (code "45") (name "Net-(IN1LEVEL-3)") (class "Default")
      (node (ref "IN1") (pin "TIP") (pinfunction "TIP_TIP") (pintype "passive"))
      (node (ref "IN1LEVEL") (pin "P$3") (pinfunction "3_P$3") (pintype "passive"))
    )
    (net (code "46") (name "Net-(IN2LEVEL-2)") (class "Default")
      (node (ref "IN2LEVEL") (pin "P$2") (pinfunction "2_P$2") (pintype "passive"))
      (node (ref "R56") (pin "2") (pinfunction "2_2") (pintype "passive"))
    )
    (net (code "47") (name "Net-(IN2LEVEL-3)") (class "Default")
      (node (ref "IN2") (pin "TIP") (pinfunction "TIP_TIP") (pintype "passive"))
      (node (ref "IN2LEVEL") (pin "P$3") (pinfunction "3_P$3") (pintype "passive"))
    )
    (net (code "48") (name "Net-(IN3LEVEL-2)") (class "Default")
      (node (ref "IN3LEVEL") (pin "P$2") (pinfunction "2_P$2") (pintype "passive"))
      (node (ref "R62") (pin "2") (pinfunction "2_2") (pintype "passive"))
    )
    (net (code "49") (name "Net-(IN3LEVEL-3)") (class "Default")
      (node (ref "IN3") (pin "TIP") (pinfunction "TIP_TIP") (pintype "passive"))
      (node (ref "IN3LEVEL") (pin "P$3") (pinfunction "3_P$3") (pintype "passive"))
    )
    (net (code "50") (name "Net-(INPUT_MIX-3)") (class "Default")
      (node (ref "INPUT_MIX") (pin "P3") (pinfunction "3_P3") (pintype "passive"))
      (node (ref "R79") (pin "1") (pinfunction "1_1") (pintype "passive"))
    )
    (net (code "51") (name "Net-(IN_GAIN-3)") (class "Default")
      (node (ref "IN_GAIN") (pin "P$3") (pinfunction "3_P$3") (pintype "passive"))
      (node (ref "R5") (pin "1") (pinfunction "1_1") (pintype "passive"))
    )
    (net (code "52") (name "Net-(LED1A-A)") (class "Default")
      (node (ref "LED1") (pin "2") (pinfunction "A_2") (pintype "passive"))
      (node (ref "LED1") (pin "3") (pinfunction "C_3") (pintype "passive"))
      (node (ref "R1") (pin "1") (pinfunction "1_1") (pintype "passive"))
    )
    (net (code "53") (name "Net-(LED2A-A)") (class "Default")
      (node (ref "LED2") (pin "2") (pinfunction "A_2") (pintype "passive"))
      (node (ref "LED2") (pin "3") (pinfunction "C_3") (pintype "passive"))
      (node (ref "R4") (pin "1") (pinfunction "1_1") (pintype "passive"))
    )
    (net (code "54") (name "Net-(OUTPUT1-3)") (class "Default")
      (node (ref "OUTPUT1") (pin "P3") (pinfunction "3_P3") (pintype "passive"))
      (node (ref "R57") (pin "2") (pinfunction "2_2") (pintype "passive"))
    )
    (net (code "55") (name "Net-(OUTPUT2-3)") (class "Default")
      (node (ref "OUTPUT2") (pin "P3") (pinfunction "3_P3") (pintype "passive"))
      (node (ref "R10") (pin "2") (pinfunction "2_2") (pintype "passive"))
    )
    (net (code "56") (name "Net-(R3-Pad1)") (class "Default")
      (node (ref "R3") (pin "1") (pinfunction "1_1") (pintype "passive"))
      (node (ref "TR1") (pin "1") (pinfunction "1_1") (pintype "passive"))
      (node (ref "TR1") (pin "2") (pinfunction "2_2") (pintype "passive"))
    )
    (net (code "57") (name "Net-(RES-2)") (class "Default")
      (node (ref "R71") (pin "1") (pinfunction "1_1") (pintype "passive"))
      (node (ref "RES") (pin "P2") (pinfunction "2_P2") (pintype "passive"))
    )
    (net (code "58") (name "Net-(RES-3)") (class "Default")
      (node (ref "D3") (pin "A") (pinfunction "A_A") (pintype "passive"))
      (node (ref "RES") (pin "P3") (pinfunction "3_P3") (pintype "passive"))
    )
    (net (code "59") (name "Net-(V-OCT-3)") (class "Default")
      (node (ref "R59") (pin "1") (pinfunction "1_1") (pintype "passive"))
      (node (ref "V-OCT") (pin "P3") (pinfunction "3_P3") (pintype "passive"))
    )
    (net (code "60") (name "RESONANCE_CTL2") (class "Default")
      (node (ref "R39") (pin "2") (pinfunction "2_2") (pintype "passive"))
      (node (ref "RESONANCE") (pin "P$2") (pinfunction "S_P$2") (pintype "passive"))
    )
    (net (code "61") (name "RESONANCE_IN2") (class "Default")
      (node (ref "IC4") (pin "8") (pinfunction "OUT_8") (pintype "output"))
      (node (ref "IC4") (pin "9") (pinfunction "-IN_9") (pintype "input"))
      (node (ref "RESONANCE") (pin "P$1") (pinfunction "E_P$1") (pintype "passive"))
    )
    (net (code "62") (name "unconnected-(IN1-SWITCH-PadNORM)") (class "Default")
      (node (ref "IN1") (pin "NORM") (pinfunction "SWITCH_NORM") (pintype "passive"))
    )
    (net (code "63") (name "unconnected-(IN2-SWITCH-PadNORM)") (class "Default")
      (node (ref "IN2") (pin "NORM") (pinfunction "SWITCH_NORM") (pintype "passive"))
    )
    (net (code "64") (name "unconnected-(IN3-SWITCH-PadNORM)") (class "Default")
      (node (ref "IN3") (pin "NORM") (pinfunction "SWITCH_NORM") (pintype "passive"))
    )
    (net (code "65") (name "unconnected-(INPUT_MIX-2-PadP2)") (class "Default")
      (node (ref "INPUT_MIX") (pin "P2") (pinfunction "2_P2") (pintype "passive"))
    )
    (net (code "66") (name "unconnected-(OUTPUT1-2-PadP2)") (class "Default")
      (node (ref "OUTPUT1") (pin "P2") (pinfunction "2_P2") (pintype "passive"))
    )
    (net (code "67") (name "unconnected-(OUTPUT2-2-PadP2)") (class "Default")
      (node (ref "OUTPUT2") (pin "P2") (pinfunction "2_P2") (pintype "passive"))
    )
  )
)
